# pc_kalam32_dev.net
KiCad netlist of a schematic drawn in EAGLE
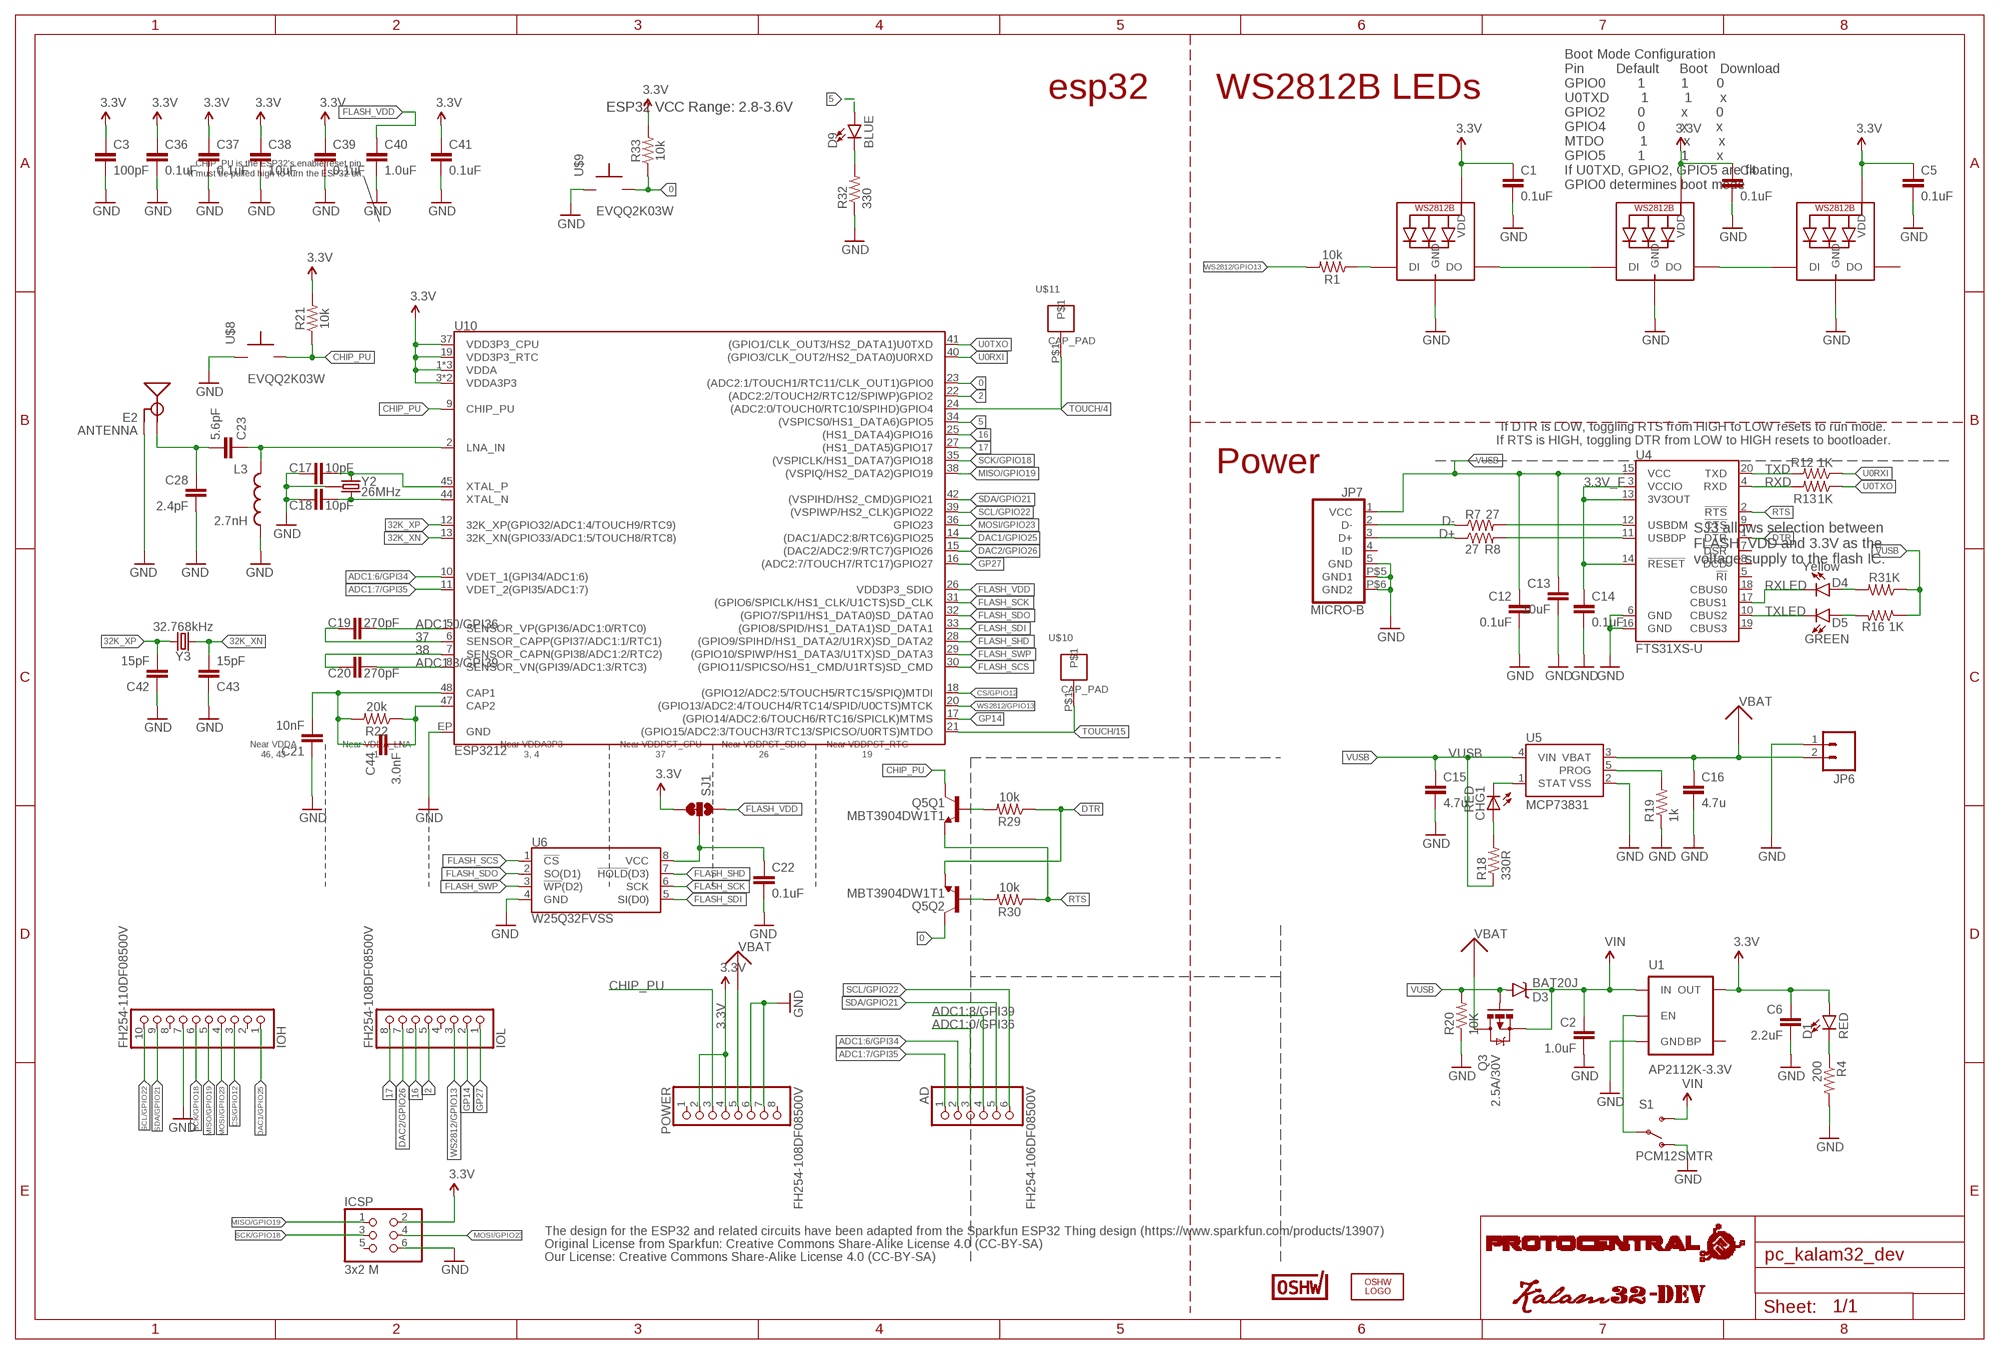
[diagram p0: schematic, sheet 1]

(export (version "E")
  (design (tool "Eeschema 10.0.6"))
  (components
    (comp (ref "AD")
      (value "FH254-106DF08500V")
      (footprint "eagle-import:1X06")
      (fields (field (name "PART_NUMBER") "20TW-535"))
      (libsource (lib "eagle-import") (part "1682_20TW-535_STD"))
    )
    (comp (ref "C1")
      (value "0.1uF")
      (footprint "eagle-import:0603")
      (libsource (lib "eagle-import") (part "0.1UF-0603-25V-(+80/-20%)"))
    )
    (comp (ref "C2")
      (value "1.0uF")
      (footprint "eagle-import:C0402")
      (libsource (lib "eagle-import") (part "C-EUC0402"))
    )
    (comp (ref "C3")
      (value "100pF")
      (footprint "eagle-import:0603")
      (libsource (lib "eagle-import") (part "100PF-0603-50V-5%"))
    )
    (comp (ref "C4")
      (value "0.1uF")
      (footprint "eagle-import:0603")
      (libsource (lib "eagle-import") (part "0.1UF-0603-25V-(+80/-20%)"))
    )
    (comp (ref "C5")
      (value "0.1uF")
      (footprint "eagle-import:0603")
      (libsource (lib "eagle-import") (part "0.1UF-0603-25V-(+80/-20%)"))
    )
    (comp (ref "C6")
      (value "2.2uF")
      (footprint "eagle-import:0603-CAP@1")
      (libsource (lib "eagle-import") (part "2.2UF-10V-20%(0603)"))
    )
    (comp (ref "C12")
      (value "0.1uF")
      (footprint "eagle-import:C0402")
      (libsource (lib "eagle-import") (part "C-EUC0402"))
    )
    (comp (ref "C13")
      (value "10uF")
      (footprint "eagle-import:C0805")
      (libsource (lib "eagle-import") (part "C-EUC0805"))
    )
    (comp (ref "C14")
      (value "0.1uF")
      (footprint "eagle-import:C0402")
      (libsource (lib "eagle-import") (part "C-EUC0402"))
    )
    (comp (ref "C15")
      (value "4.7u")
      (footprint "eagle-import:C0805")
      (libsource (lib "eagle-import") (part "C-EUC0805"))
    )
    (comp (ref "C16")
      (value "4.7u")
      (footprint "eagle-import:C0805")
      (libsource (lib "eagle-import") (part "C-EUC0805"))
    )
    (comp (ref "C17")
      (value "10pF")
      (footprint "eagle-import:0603")
      (libsource (lib "eagle-import") (part "10PF-0603-50V-5%"))
    )
    (comp (ref "C18")
      (value "10pF")
      (footprint "eagle-import:0603")
      (libsource (lib "eagle-import") (part "10PF-0603-50V-5%"))
    )
    (comp (ref "C19")
      (value "270pF")
      (footprint "eagle-import:0603")
      (libsource (lib "eagle-import") (part "270PF-50V-5%(0603)"))
    )
    (comp (ref "C20")
      (value "270pF")
      (footprint "eagle-import:0603")
      (libsource (lib "eagle-import") (part "270PF-50V-5%(0603)"))
    )
    (comp (ref "C21")
      (value "10nF")
      (footprint "eagle-import:0603")
      (libsource (lib "eagle-import") (part "10NF-0603-50V-10%"))
    )
    (comp (ref "C22")
      (value "0.1uF")
      (footprint "eagle-import:0603")
      (libsource (lib "eagle-import") (part "0.1UF-0603-25V-(+80/-20%)"))
    )
    (comp (ref "C23")
      (value "5.6pF")
      (footprint "eagle-import:0603")
      (libsource (lib "eagle-import") (part "5.6PF-50V-5%(0603)"))
    )
    (comp (ref "C28")
      (value "2.4pF")
      (footprint "eagle-import:0603")
      (libsource (lib "eagle-import") (part "2.4PF-0603-50V-5%"))
    )
    (comp (ref "C36")
      (value "0.1uF")
      (footprint "eagle-import:0603")
      (libsource (lib "eagle-import") (part "0.1UF-0603-25V-(+80/-20%)"))
    )
    (comp (ref "C37")
      (value "0.1uF")
      (footprint "eagle-import:0603")
      (libsource (lib "eagle-import") (part "0.1UF-0603-25V-(+80/-20%)"))
    )
    (comp (ref "C38")
      (value "10uF")
      (footprint "eagle-import:0603")
      (libsource (lib "eagle-import") (part "10UF-0603-6.3V-20%"))
    )
    (comp (ref "C39")
      (value "0.1uF")
      (footprint "eagle-import:0603")
      (libsource (lib "eagle-import") (part "0.1UF-0603-25V-(+80/-20%)"))
    )
    (comp (ref "C40")
      (value "1.0uF")
      (footprint "eagle-import:0603")
      (libsource (lib "eagle-import") (part "1.0UF-0603-16V-10%"))
    )
    (comp (ref "C41")
      (value "0.1uF")
      (footprint "eagle-import:0603")
      (libsource (lib "eagle-import") (part "0.1UF-0603-25V-(+80/-20%)"))
    )
    (comp (ref "C42")
      (value "15pF")
      (footprint "eagle-import:0603")
      (libsource (lib "eagle-import") (part "15PF-0603-50V-5%"))
    )
    (comp (ref "C43")
      (value "15pF")
      (footprint "eagle-import:0603")
      (libsource (lib "eagle-import") (part "15PF-0603-50V-5%"))
    )
    (comp (ref "C44")
      (value "3.0nF")
      (footprint "eagle-import:0603")
      (libsource (lib "eagle-import") (part "3.0NF-0603-50V-5%"))
    )
    (comp (ref "CHG1")
      (value "RED")
      (footprint "eagle-import:CHIPLED_0603")
      (libsource (lib "eagle-import") (part "LEDCHIPLED_0603"))
    )
    (comp (ref "D1")
      (value "RED")
      (footprint "eagle-import:LED-0603")
      (libsource (lib "eagle-import") (part "LED-RED0603"))
    )
    (comp (ref "D3")
      (value "BAT20J")
      (footprint "eagle-import:SOD-323")
      (libsource (lib "eagle-import") (part "DIODE-SCHOTTKY-BAT20J"))
    )
    (comp (ref "D4")
      (value "Yellow")
      (footprint "eagle-import:LED-0603")
      (libsource (lib "eagle-import") (part "LED-YELLOW0603"))
    )
    (comp (ref "D5")
      (value "GREEN")
      (footprint "eagle-import:LED-0603@1")
      (libsource (lib "eagle-import") (part "LED-GREEN0603"))
    )
    (comp (ref "D9")
      (value "BLUE")
      (footprint "eagle-import:LED-0603")
      (libsource (lib "eagle-import") (part "LED-BLUE0603"))
    )
    (comp (ref "E2")
      (value "ANTENNA")
      (footprint "eagle-import:TRACE_ANTENNA_2.4GHZ_25.7MM_TUNED")
      (libsource (lib "eagle-import") (part "ANTENNATRACE-TUNED"))
    )
    (comp (ref "ICSP")
      (value "3x2 M")
      (footprint "eagle-import:2X03")
      (fields (field (name "PART_NUMBER") "PH254-203DF118A00V"))
      (libsource (lib "eagle-import") (part "0114_PH254-203DF118A00V"))
    )
    (comp (ref "IOH")
      (value "FH254-110DF08500V")
      (footprint "eagle-import:1X10")
      (fields (field (name "PART_NUMBER") "20TW-537"))
      (libsource (lib "eagle-import") (part "1684_20TW-537"))
    )
    (comp (ref "IOL")
      (value "FH254-108DF08500V")
      (footprint "eagle-import:1X08")
      (fields (field (name "PART_NUMBER") "20TW-536"))
      (libsource (lib "eagle-import") (part "1683_20TW-536"))
    )
    (comp (ref "JP6")
      (value "M02-JST-2MM-SMT")
      (footprint "eagle-import:JST-2-SMD")
      (libsource (lib "eagle-import") (part "M02-JST-2MM-SMT"))
    )
    (comp (ref "JP7")
      (value "MICRO-B")
      (footprint "eagle-import:MICRO-B")
      (libsource (lib "eagle-import") (part "MICRO-B"))
    )
    (comp (ref "L3")
      (value "2.7nH")
      (footprint "eagle-import:0603")
      (libsource (lib "eagle-import") (part "INDUCTOR0603"))
    )
    (comp (ref "LED1")
      (value "WS2812B5050")
      (footprint "eagle-import:WS2812B")
      (libsource (lib "eagle-import") (part "WS2812B5050"))
    )
    (comp (ref "LED2")
      (value "WS2812B5050")
      (footprint "eagle-import:WS2812B")
      (libsource (lib "eagle-import") (part "WS2812B5050"))
    )
    (comp (ref "LED3")
      (value "WS2812B5050")
      (footprint "eagle-import:WS2812B")
      (libsource (lib "eagle-import") (part "WS2812B5050"))
    )
    (comp (ref "LOGO2")
      (value "OSHW_LOGO_FILLX0200-NT")
      (footprint "eagle-import:OSHW_FILLX200_NOTEXT")
      (libsource (lib "eagle-import") (part "OSHW_LOGO_FILLX0200-NT"))
    )
    (comp (ref "POWER")
      (value "FH254-108DF08500V")
      (footprint "eagle-import:1X08")
      (fields (field (name "PART_NUMBER") "20TW-536"))
      (libsource (lib "eagle-import") (part "1683_20TW-536"))
    )
    (comp (ref "Q3")
      (value "2.5A/30V")
      (footprint "eagle-import:SOT23-3")
      (libsource (lib "eagle-import") (part "MOSFET-PCHANNELDMG2307L"))
    )
    (comp (ref "Q5")
      (value "MBT3904DW1T1")
      (footprint "eagle-import:SC70-6")
      (libsource (lib "eagle-import") (part "MBT3904DW1T1"))
    )
    (comp (ref "R1")
      (value "10k")
      (footprint "eagle-import:0603")
      (libsource (lib "eagle-import") (part "10KOHM-1/10W-1%(0603)0603"))
    )
    (comp (ref "R3")
      (value "1K")
      (footprint "eagle-import:R0402")
      (libsource (lib "eagle-import") (part "R-US_R0402"))
    )
    (comp (ref "R4")
      (value "200")
      (footprint "eagle-import:R0402")
      (libsource (lib "eagle-import") (part "R-US_R0402"))
    )
    (comp (ref "R7")
      (value "27")
      (footprint "eagle-import:R0402")
      (libsource (lib "eagle-import") (part "R-US_R0402"))
    )
    (comp (ref "R8")
      (value "27")
      (footprint "eagle-import:R0402")
      (libsource (lib "eagle-import") (part "R-US_R0402"))
    )
    (comp (ref "R12")
      (value "1K")
      (footprint "eagle-import:R0402")
      (libsource (lib "eagle-import") (part "R-US_R0402"))
    )
    (comp (ref "R13")
      (value "1K")
      (footprint "eagle-import:R0402")
      (libsource (lib "eagle-import") (part "R-US_R0402"))
    )
    (comp (ref "R16")
      (value "1K")
      (footprint "eagle-import:R0402")
      (libsource (lib "eagle-import") (part "R-US_R0402"))
    )
    (comp (ref "R18")
      (value "330R")
      (footprint "eagle-import:R0402")
      (libsource (lib "eagle-import") (part "R-US_R0402"))
    )
    (comp (ref "R19")
      (value "1k")
      (footprint "eagle-import:R0402")
      (libsource (lib "eagle-import") (part "R-US_R0402"))
    )
    (comp (ref "R20")
      (value "10K")
      (footprint "eagle-import:R0402")
      (libsource (lib "eagle-import") (part "R-US_R0402"))
    )
    (comp (ref "R21")
      (value "10k")
      (footprint "eagle-import:0603")
      (libsource (lib "eagle-import") (part "10KOHM-1/10W-1%(0603)0603"))
    )
    (comp (ref "R22")
      (value "20k")
      (footprint "eagle-import:0603")
      (libsource (lib "eagle-import") (part "20KOHM-0603-1/10W-1%"))
    )
    (comp (ref "R29")
      (value "10k")
      (footprint "eagle-import:0603")
      (libsource (lib "eagle-import") (part "10KOHM-0603-1/10W-1%"))
    )
    (comp (ref "R30")
      (value "10k")
      (footprint "eagle-import:0603")
      (libsource (lib "eagle-import") (part "10KOHM-0603-1/10W-1%"))
    )
    (comp (ref "R32")
      (value "330")
      (footprint "eagle-import:R0805")
      (libsource (lib "eagle-import") (part "R-US_R0805"))
    )
    (comp (ref "R33")
      (value "10k")
      (footprint "eagle-import:0603")
      (libsource (lib "eagle-import") (part "10KOHM-1/10W-1%(0603)0603"))
    )
    (comp (ref "S1")
      (value "PCM12SMTR")
      (footprint "eagle-import:SWITCH-SPST-SMD-A")
      (libsource (lib "eagle-import") (part "SWITCH-SPDT-SMD-A"))
    )
    (comp (ref "SJ1")
      (value "JUMPER-PAD-3-2OF3_NC_BY_TRACE_SMALL")
      (footprint "eagle-import:PAD-JUMPER-3-2OF3_NC_BY_TRACE_YES_SILK_FULL_BOX")
      (libsource (lib "eagle-import") (part "JUMPER-PAD-3-2OF3_NC_BY_TRACE_SMALL"))
    )
    (comp (ref "U$5")
      (value "CERT-MEDIUM")
      (footprint "eagle-import:CERT-MED-SILK")
      (libsource (lib "eagle-import") (part "CERT-MEDIUM"))
    )
    (comp (ref "U$8")
      (value "EVQQ2K03W")
      (footprint "eagle-import:EVQQ2")
      (libsource (lib "eagle-import") (part "EVQQ2K03W"))
    )
    (comp (ref "U$9")
      (value "EVQQ2K03W")
      (footprint "eagle-import:EVQQ2")
      (libsource (lib "eagle-import") (part "EVQQ2K03W"))
    )
    (comp (ref "U$10")
      (value "CAP_PAD")
      (footprint "eagle-import:CAP_PAD")
      (libsource (lib "eagle-import") (part "CAP_PAD"))
    )
    (comp (ref "U$11")
      (value "CAP_PAD")
      (footprint "eagle-import:CAP_PAD")
      (libsource (lib "eagle-import") (part "CAP_PAD"))
    )
    (comp (ref "U$12")
      (value "KALAM32-DEV")
      (footprint "eagle-import:KALAM32-DEV")
      (libsource (lib "eagle-import") (part "KALAM32-DEV"))
    )
    (comp (ref "U$13")
      (value "PROTY_LOGO_WITH_TEXT")
      (footprint "eagle-import:PROTY_WITH_TEXT")
      (libsource (lib "eagle-import") (part "PROTY_LOGO_WITH_TEXT"))
    )
    (comp (ref "U1")
      (value "AP2112K-3.3V")
      (footprint "eagle-import:SOT23-5")
      (libsource (lib "eagle-import") (part "V_REG_LDOSMD"))
    )
    (comp (ref "U4")
      (value "FTS31XS-U")
      (footprint "eagle-import:SSOP20_L")
      (libsource (lib "eagle-import") (part "FT231XS"))
    )
    (comp (ref "U5")
      (value "MCP73831")
      (footprint "eagle-import:SOT23-5")
      (libsource (lib "eagle-import") (part "MCP73831"))
    )
    (comp (ref "U6")
      (value "W25Q32FVSS")
      (footprint "eagle-import:SOIC-8")
      (libsource (lib "eagle-import") (part "W25Q32FVSS"))
    )
    (comp (ref "U10")
      (value "ESP3212")
      (footprint "eagle-import:QFN48-0.4MM")
      (libsource (lib "eagle-import") (part "ESP3212"))
    )
    (comp (ref "Y2")
      (value "26MHz")
      (footprint "eagle-import:CRYSTAL-SMD-3.2X2.5")
      (libsource (lib "eagle-import") (part "CRYSTAL-GROUNDED3.2X2.5"))
    )
    (comp (ref "Y3")
      (value "32.768kHz")
      (footprint "eagle-import:CRYSTAL-SMD-3.2X1.5MM")
      (libsource (lib "eagle-import") (part "CRYSTAL-32.768KHZSMD-3.2X1.5"))
    )
  )
  (nets
    (net (code "1") (name "/3.3V_F") (class "Default")
      (node (ref "C14") (pin "1") (pinfunction "1_1") (pintype "passive"))
      (node (ref "U4") (pin "13") (pinfunction "3V3OUT_13") (pintype "bidirectional"))
      (node (ref "U4") (pin "14") (pinfunction "~{RESET}_14") (pintype "bidirectional"))
      (node (ref "U4") (pin "3") (pinfunction "VCCIO_3") (pintype "bidirectional"))
    )
    (net (code "2") (name "/37") (class "Default")
      (node (ref "C19") (pin "1") (pinfunction "1_1") (pintype "passive"))
      (node (ref "U10") (pin "6") (pinfunction "SENSOR_CAPP(GPI37/ADC1:1/RTC1)_6") (pintype "bidirectional"))
    )
    (net (code "3") (name "/38") (class "Default")
      (node (ref "C20") (pin "1") (pinfunction "1_1") (pintype "passive"))
      (node (ref "U10") (pin "7") (pinfunction "SENSOR_CAPN(GPI38/ADC1:2/RTC2)_7") (pintype "bidirectional"))
    )
    (net (code "4") (name "/ADC1:0{slash}GPI36") (class "Default")
      (node (ref "AD") (pin "3") (pinfunction "3_3") (pintype "passive"))
      (node (ref "C19") (pin "2") (pinfunction "2_2") (pintype "passive"))
      (node (ref "U10") (pin "5") (pinfunction "SENSOR_VP(GPI36/ADC1:0/RTC0)_5") (pintype "bidirectional"))
    )
    (net (code "5") (name "/ADC1:3{slash}GPI39") (class "Default")
      (node (ref "AD") (pin "4") (pinfunction "4_4") (pintype "passive"))
      (node (ref "C20") (pin "2") (pinfunction "2_2") (pintype "passive"))
      (node (ref "U10") (pin "8") (pinfunction "SENSOR_VN(GPI39/ADC1:3/RTC3)_8") (pintype "bidirectional"))
    )
    (net (code "6") (name "/D+") (class "Default")
      (node (ref "JP7") (pin "3") (pinfunction "D+_3") (pintype "bidirectional"))
      (node (ref "R8") (pin "1") (pinfunction "1_1") (pintype "passive"))
    )
    (net (code "7") (name "/D-") (class "Default")
      (node (ref "JP7") (pin "2") (pinfunction "D-_2") (pintype "bidirectional"))
      (node (ref "R7") (pin "1") (pinfunction "1_1") (pintype "passive"))
    )
    (net (code "8") (name "/RXD") (class "Default")
      (node (ref "R13") (pin "2") (pinfunction "2_2") (pintype "passive"))
      (node (ref "U4") (pin "4") (pinfunction "RXD_4") (pintype "bidirectional"))
    )
    (net (code "9") (name "/RXLED") (class "Default")
      (node (ref "D4") (pin "C") (pinfunction "C_C") (pintype "passive"))
      (node (ref "U4") (pin "17") (pinfunction "CBUS1_17") (pintype "bidirectional"))
    )
    (net (code "10") (name "/TXD") (class "Default")
      (node (ref "R12") (pin "2") (pinfunction "2_2") (pintype "passive"))
      (node (ref "U4") (pin "20") (pinfunction "TXD_20") (pintype "bidirectional"))
    )
    (net (code "11") (name "/TXLED") (class "Default")
      (node (ref "D5") (pin "C") (pinfunction "C_C") (pintype "passive"))
      (node (ref "U4") (pin "10") (pinfunction "CBUS2_10") (pintype "bidirectional"))
    )
    (net (code "12") (name "0") (class "Default")
      (node (ref "Q5") (pin "6") (pinfunction "C_6") (pintype "passive"))
      (node (ref "R33") (pin "1") (pinfunction "1_1") (pintype "passive"))
      (node (ref "U$9") (pin "P$3") (pinfunction "P$2_P$3") (pintype "bidirectional"))
      (node (ref "U10") (pin "23") (pinfunction "(ADC2:1/TOUCH1/RTC11/CLK_OUT1)GPIO0_23") (pintype "bidirectional"))
    )
    (net (code "13") (name "2") (class "Default")
      (node (ref "IOL") (pin "5") (pinfunction "5_5") (pintype "passive"))
      (node (ref "U10") (pin "22") (pinfunction "(ADC2:2/TOUCH2/RTC12/SPIWP)GPIO2_22") (pintype "bidirectional"))
    )
    (net (code "14") (name "3.3V") (class "Default")
      (node (ref "C1") (pin "1") (pinfunction "1_1") (pintype "passive"))
      (node (ref "C3") (pin "1") (pinfunction "1_1") (pintype "passive"))
      (node (ref "C36") (pin "1") (pinfunction "1_1") (pintype "passive"))
      (node (ref "C37") (pin "1") (pinfunction "1_1") (pintype "passive"))
      (node (ref "C38") (pin "1") (pinfunction "1_1") (pintype "passive"))
      (node (ref "C39") (pin "1") (pinfunction "1_1") (pintype "passive"))
      (node (ref "C4") (pin "1") (pinfunction "1_1") (pintype "passive"))
      (node (ref "C41") (pin "1") (pinfunction "1_1") (pintype "passive"))
      (node (ref "C5") (pin "1") (pinfunction "1_1") (pintype "passive"))
      (node (ref "C6") (pin "1") (pinfunction "1_1") (pintype "passive"))
      (node (ref "D1") (pin "A") (pinfunction "A_A") (pintype "passive"))
      (node (ref "ICSP") (pin "2") (pinfunction "2_2") (pintype "passive"))
      (node (ref "LED1") (pin "1-VDD") (pinfunction "VDD_1-VDD") (pintype "power_in"))
      (node (ref "LED2") (pin "1-VDD") (pinfunction "VDD_1-VDD") (pintype "power_in"))
      (node (ref "LED3") (pin "1-VDD") (pinfunction "VDD_1-VDD") (pintype "power_in"))
      (node (ref "POWER") (pin "2") (pinfunction "2_2") (pintype "passive"))
      (node (ref "POWER") (pin "4") (pinfunction "4_4") (pintype "passive"))
      (node (ref "R21") (pin "2") (pinfunction "2_2") (pintype "passive"))
      (node (ref "R33") (pin "2") (pinfunction "2_2") (pintype "passive"))
      (node (ref "SJ1") (pin "3") (pinfunction "3_3") (pintype "passive"))
      (node (ref "U1") (pin "5") (pinfunction "OUT_5") (pintype "passive"))
      (node (ref "U10") (pin "1") (pinfunction "VDDA_1") (pintype "bidirectional"))
      (node (ref "U10") (pin "19") (pinfunction "VDD3P3_RTC_19") (pintype "bidirectional"))
      (node (ref "U10") (pin "3") (pinfunction "VDDA3P3_3") (pintype "bidirectional"))
      (node (ref "U10") (pin "37") (pinfunction "VDD3P3_CPU_37") (pintype "bidirectional"))
      (node (ref "U10") (pin "4") (pinfunction "VDDA3P3_4") (pintype "bidirectional"))
      (node (ref "U10") (pin "43") (pinfunction "VDDA_43") (pintype "bidirectional"))
      (node (ref "U10") (pin "46") (pinfunction "VDDA_46") (pintype "bidirectional"))
    )
    (net (code "15") (name "5") (class "Default")
      (node (ref "D9") (pin "A") (pinfunction "A_A") (pintype "passive"))
      (node (ref "U10") (pin "34") (pinfunction "(VSPICS0/HS1_DATA6)GPIO5_34") (pintype "bidirectional"))
    )
    (net (code "16") (name "16") (class "Default")
      (node (ref "IOL") (pin "6") (pinfunction "6_6") (pintype "passive"))
      (node (ref "U10") (pin "25") (pinfunction "(HS1_DATA4)GPIO16_25") (pintype "bidirectional"))
    )
    (net (code "17") (name "17") (class "Default")
      (node (ref "IOL") (pin "8") (pinfunction "8_8") (pintype "passive"))
      (node (ref "U10") (pin "27") (pinfunction "(HS1_DATA5)GPIO17_27") (pintype "bidirectional"))
    )
    (net (code "18") (name "32K_XN") (class "Default")
      (node (ref "C43") (pin "2") (pinfunction "2_2") (pintype "passive"))
      (node (ref "U10") (pin "13") (pinfunction "32K_XN(GPIO33/ADC1:5/TOUCH8/RTC8)_13") (pintype "bidirectional"))
      (node (ref "Y3") (pin "P$2") (pinfunction "2_P$2") (pintype "passive"))
    )
    (net (code "19") (name "32K_XP") (class "Default")
      (node (ref "C42") (pin "2") (pinfunction "2_2") (pintype "passive"))
      (node (ref "U10") (pin "12") (pinfunction "32K_XP(GPIO32/ADC1:4/TOUCH9/RTC9)_12") (pintype "bidirectional"))
      (node (ref "Y3") (pin "P$1") (pinfunction "1_P$1") (pintype "passive"))
    )
    (net (code "20") (name "ADC1:6{slash}GPI34") (class "Default")
      (node (ref "AD") (pin "2") (pinfunction "2_2") (pintype "passive"))
      (node (ref "U10") (pin "10") (pinfunction "VDET_1(GPI34/ADC1:6)_10") (pintype "bidirectional"))
    )
    (net (code "21") (name "ADC1:7{slash}GPI35") (class "Default")
      (node (ref "AD") (pin "1") (pinfunction "1_1") (pintype "passive"))
      (node (ref "U10") (pin "11") (pinfunction "VDET_2(GPI35/ADC1:7)_11") (pintype "bidirectional"))
    )
    (net (code "22") (name "CHIP_PU") (class "Default")
      (node (ref "POWER") (pin "3") (pinfunction "3_3") (pintype "passive"))
      (node (ref "Q5") (pin "3") (pinfunction "C_3") (pintype "passive"))
      (node (ref "R21") (pin "1") (pinfunction "1_1") (pintype "passive"))
      (node (ref "U$8") (pin "P$3") (pinfunction "P$2_P$3") (pintype "bidirectional"))
      (node (ref "U10") (pin "9") (pinfunction "CHIP_PU_9") (pintype "bidirectional"))
    )
    (net (code "23") (name "CS{slash}GPIO12") (class "Default")
      (node (ref "IOH") (pin "3") (pinfunction "3_3") (pintype "passive"))
      (node (ref "U10") (pin "18") (pinfunction "(GPIO12/ADC2:5/TOUCH5/RTC15/SPIQ)MTDI_18") (pintype "bidirectional"))
    )
    (net (code "24") (name "DAC1{slash}GPIO25") (class "Default")
      (node (ref "IOH") (pin "1") (pinfunction "1_1") (pintype "passive"))
      (node (ref "U10") (pin "14") (pinfunction "(DAC1/ADC2:8/RTC6)GPIO25_14") (pintype "bidirectional"))
    )
    (net (code "25") (name "DAC2{slash}GPIO26") (class "Default")
      (node (ref "IOL") (pin "7") (pinfunction "7_7") (pintype "passive"))
      (node (ref "U10") (pin "15") (pinfunction "(DAC2/ADC2:9/RTC7)GPIO26_15") (pintype "bidirectional"))
    )
    (net (code "26") (name "DTR") (class "Default")
      (node (ref "Q5") (pin "1") (pinfunction "E_1") (pintype "passive"))
      (node (ref "R29") (pin "1") (pinfunction "1_1") (pintype "passive"))
      (node (ref "U4") (pin "1") (pinfunction "~{DTR}_1") (pintype "bidirectional"))
    )
    (net (code "27") (name "FLASH_SCK") (class "Default")
      (node (ref "U10") (pin "31") (pinfunction "(GPIO6/SPICLK/HS1_CLK/U1CTS)SD_CLK_31") (pintype "bidirectional"))
      (node (ref "U6") (pin "6") (pinfunction "SCK_6") (pintype "bidirectional"))
    )
    (net (code "28") (name "FLASH_SCS") (class "Default")
      (node (ref "U10") (pin "30") (pinfunction "(GPIO11/SPICSO/HS1_CMD/U1RTS)SD_CMD_30") (pintype "bidirectional"))
      (node (ref "U6") (pin "1") (pinfunction "~{CS}_1") (pintype "bidirectional"))
    )
    (net (code "29") (name "FLASH_SDI") (class "Default")
      (node (ref "U10") (pin "33") (pinfunction "(GPIO8/SPID/HS1_DATA1)SD_DATA1_33") (pintype "bidirectional"))
      (node (ref "U6") (pin "5") (pinfunction "SI(D0)_5") (pintype "bidirectional"))
    )
    (net (code "30") (name "FLASH_SDO") (class "Default")
      (node (ref "U10") (pin "32") (pinfunction "(GPIO7/SPI1/HS1_DATA0)SD_DATA0_32") (pintype "bidirectional"))
      (node (ref "U6") (pin "2") (pinfunction "SO(D1)_2") (pintype "bidirectional"))
    )
    (net (code "31") (name "FLASH_SHD") (class "Default")
      (node (ref "U10") (pin "28") (pinfunction "(GPIO9/SPIHD/HS1_DATA2/U1RX)SD_DATA2_28") (pintype "bidirectional"))
      (node (ref "U6") (pin "7") (pinfunction "~{HOLD}(D3)_7") (pintype "bidirectional"))
    )
    (net (code "32") (name "FLASH_SWP") (class "Default")
      (node (ref "U10") (pin "29") (pinfunction "(GPIO10/SPIWP/HS1_DATA3/U1TX)SD_DATA3_29") (pintype "bidirectional"))
      (node (ref "U6") (pin "3") (pinfunction "~{WP}(D2)_3") (pintype "bidirectional"))
    )
    (net (code "33") (name "FLASH_VDD") (class "Default")
      (node (ref "C40") (pin "1") (pinfunction "1_1") (pintype "passive"))
      (node (ref "SJ1") (pin "1") (pinfunction "1_1") (pintype "passive"))
      (node (ref "U10") (pin "26") (pinfunction "VDD3P3_SDIO_26") (pintype "bidirectional"))
    )
    (net (code "34") (name "GND") (class "Default")
      (node (ref "C1") (pin "2") (pinfunction "2_2") (pintype "passive"))
      (node (ref "C12") (pin "2") (pinfunction "2_2") (pintype "passive"))
      (node (ref "C13") (pin "2") (pinfunction "2_2") (pintype "passive"))
      (node (ref "C14") (pin "2") (pinfunction "2_2") (pintype "passive"))
      (node (ref "C15") (pin "2") (pinfunction "2_2") (pintype "passive"))
      (node (ref "C16") (pin "2") (pinfunction "2_2") (pintype "passive"))
      (node (ref "C17") (pin "1") (pinfunction "1_1") (pintype "passive"))
      (node (ref "C18") (pin "1") (pinfunction "1_1") (pintype "passive"))
      (node (ref "C2") (pin "2") (pinfunction "2_2") (pintype "passive"))
      (node (ref "C21") (pin "1") (pinfunction "1_1") (pintype "passive"))
      (node (ref "C22") (pin "2") (pinfunction "2_2") (pintype "passive"))
      (node (ref "C28") (pin "2") (pinfunction "2_2") (pintype "passive"))
      (node (ref "C3") (pin "2") (pinfunction "2_2") (pintype "passive"))
      (node (ref "C36") (pin "2") (pinfunction "2_2") (pintype "passive"))
      (node (ref "C37") (pin "2") (pinfunction "2_2") (pintype "passive"))
      (node (ref "C38") (pin "2") (pinfunction "2_2") (pintype "passive"))
      (node (ref "C39") (pin "2") (pinfunction "2_2") (pintype "passive"))
      (node (ref "C4") (pin "2") (pinfunction "2_2") (pintype "passive"))
      (node (ref "C40") (pin "2") (pinfunction "2_2") (pintype "passive"))
      (node (ref "C41") (pin "2") (pinfunction "2_2") (pintype "passive"))
      (node (ref "C42") (pin "1") (pinfunction "1_1") (pintype "passive"))
      (node (ref "C43") (pin "1") (pinfunction "1_1") (pintype "passive"))
      (node (ref "C5") (pin "2") (pinfunction "2_2") (pintype "passive"))
      (node (ref "C6") (pin "2") (pinfunction "2_2") (pintype "passive"))
      (node (ref "E2") (pin "GND") (pinfunction "GND_GND") (pintype "bidirectional"))
      (node (ref "E2") (pin "GND2") (pinfunction "GND_GND2") (pintype "bidirectional"))
      (node (ref "ICSP") (pin "6") (pinfunction "6_6") (pintype "passive"))
      (node (ref "IOH") (pin "7") (pinfunction "7_7") (pintype "passive"))
      (node (ref "JP6") (pin "1") (pinfunction "1_1") (pintype "passive"))
      (node (ref "JP7") (pin "5") (pinfunction "GND_5") (pintype "bidirectional"))
      (node (ref "JP7") (pin "P$5") (pinfunction "GND1_P$5") (pintype "bidirectional"))
      (node (ref "JP7") (pin "P$6") (pinfunction "GND2_P$6") (pintype "bidirectional"))
      (node (ref "L3") (pin "2") (pinfunction "2_2") (pintype "passive"))
      (node (ref "LED1") (pin "3-GND") (pinfunction "GND_3-GND") (pintype "power_in"))
      (node (ref "LED2") (pin "3-GND") (pinfunction "GND_3-GND") (pintype "power_in"))
      (node (ref "LED3") (pin "3-GND") (pinfunction "GND_3-GND") (pintype "power_in"))
      (node (ref "POWER") (pin "6") (pinfunction "6_6") (pintype "passive"))
      (node (ref "POWER") (pin "7") (pinfunction "7_7") (pintype "passive"))
      (node (ref "R19") (pin "1") (pinfunction "1_1") (pintype "passive"))
      (node (ref "R20") (pin "1") (pinfunction "1_1") (pintype "passive"))
      (node (ref "R32") (pin "1") (pinfunction "1_1") (pintype "passive"))
      (node (ref "R4") (pin "2") (pinfunction "2_2") (pintype "passive"))
      (node (ref "S1") (pin "1") (pinfunction "O_1") (pintype "passive"))
      (node (ref "U$8") (pin "P$1") (pinfunction "P$1_P$1") (pintype "bidirectional"))
      (node (ref "U$9") (pin "P$1") (pinfunction "P$1_P$1") (pintype "bidirectional"))
      (node (ref "U1") (pin "2") (pinfunction "GND_2") (pintype "input"))
      (node (ref "U10") (pin "EP") (pinfunction "GND_EP") (pintype "bidirectional"))
      (node (ref "U4") (pin "16") (pinfunction "GND_16") (pintype "bidirectional"))
      (node (ref "U4") (pin "6") (pinfunction "GND_6") (pintype "bidirectional"))
      (node (ref "U5") (pin "2") (pinfunction "VSS_2") (pintype "power_in"))
      (node (ref "U6") (pin "4") (pinfunction "GND_4") (pintype "bidirectional"))
      (node (ref "Y2") (pin "2") (pinfunction "GND_2") (pintype "passive"))
      (node (ref "Y2") (pin "4") (pinfunction "GND_4") (pintype "passive"))
    )
    (net (code "35") (name "GP14") (class "Default")
      (node (ref "IOL") (pin "2") (pinfunction "2_2") (pintype "passive"))
      (node (ref "U10") (pin "17") (pinfunction "(GPIO14/ADC2:6/TOUCH6/RTC16/SPICLK)MTMS_17") (pintype "bidirectional"))
    )
    (net (code "36") (name "GP27") (class "Default")
      (node (ref "IOL") (pin "1") (pinfunction "1_1") (pintype "passive"))
      (node (ref "U10") (pin "16") (pinfunction "(ADC2:7/TOUCH7/RTC17)GPIO27_16") (pintype "bidirectional"))
    )
    (net (code "37") (name "MISO{slash}GPIO19") (class "Default")
      (node (ref "ICSP") (pin "1") (pinfunction "1_1") (pintype "passive"))
      (node (ref "IOH") (pin "5") (pinfunction "5_5") (pintype "passive"))
      (node (ref "U10") (pin "38") (pinfunction "(VSPIQ/HS2_DATA2)GPIO19_38") (pintype "bidirectional"))
    )
    (net (code "38") (name "MOSI{slash}GPIO23") (class "Default")
      (node (ref "ICSP") (pin "4") (pinfunction "4_4") (pintype "passive"))
      (node (ref "IOH") (pin "4") (pinfunction "4_4") (pintype "passive"))
      (node (ref "U10") (pin "36") (pinfunction "GPIO23_36") (pintype "bidirectional"))
    )
    (net (code "39") (name "Net-(CHG1-PadA)") (class "Default")
      (node (ref "CHG1") (pin "A") (pinfunction "A_A") (pintype "passive"))
      (node (ref "R18") (pin "2") (pinfunction "2_2") (pintype "passive"))
    )
    (net (code "40") (name "Net-(D1-PadC)") (class "Default")
      (node (ref "D1") (pin "C") (pinfunction "C_C") (pintype "passive"))
      (node (ref "R4") (pin "1") (pinfunction "1_1") (pintype "passive"))
    )
    (net (code "41") (name "Net-(D4-PadA)") (class "Default")
      (node (ref "D4") (pin "A") (pinfunction "A_A") (pintype "passive"))
      (node (ref "R3") (pin "2") (pinfunction "2_2") (pintype "passive"))
    )
    (net (code "42") (name "Net-(D5-PadA)") (class "Default")
      (node (ref "D5") (pin "A") (pinfunction "A_A") (pintype "passive"))
      (node (ref "R16") (pin "2") (pinfunction "2_2") (pintype "passive"))
    )
    (net (code "43") (name "Net-(D9-PadC)") (class "Default")
      (node (ref "D9") (pin "C") (pinfunction "C_C") (pintype "passive"))
      (node (ref "R32") (pin "2") (pinfunction "2_2") (pintype "passive"))
    )
    (net (code "44") (name "Net-(E2-SIGNAL)") (class "Default")
      (node (ref "C23") (pin "2") (pinfunction "2_2") (pintype "passive"))
      (node (ref "C28") (pin "1") (pinfunction "1_1") (pintype "passive"))
      (node (ref "E2") (pin "ANT") (pinfunction "SIGNAL_ANT") (pintype "bidirectional"))
    )
    (net (code "45") (name "Net-(LED1-DI)") (class "Default")
      (node (ref "LED1") (pin "4-DIN") (pinfunction "DI_4-DIN") (pintype "input"))
      (node (ref "R1") (pin "1") (pinfunction "1_1") (pintype "passive"))
    )
    (net (code "46") (name "Net-(LED1-DO)") (class "Default")
      (node (ref "LED1") (pin "2-DOUT") (pinfunction "DO_2-DOUT") (pintype "output"))
      (node (ref "LED2") (pin "4-DIN") (pinfunction "DI_4-DIN") (pintype "input"))
    )
    (net (code "47") (name "Net-(LED2-DO)") (class "Default")
      (node (ref "LED2") (pin "2-DOUT") (pinfunction "DO_2-DOUT") (pintype "output"))
      (node (ref "LED3") (pin "4-DIN") (pinfunction "DI_4-DIN") (pintype "input"))
    )
    (net (code "48") (name "Net-(Q5A-B)") (class "Default")
      (node (ref "Q5") (pin "5") (pinfunction "B_5") (pintype "passive"))
      (node (ref "R29") (pin "2") (pinfunction "2_2") (pintype "passive"))
    )
    (net (code "49") (name "Net-(Q5B-B)") (class "Default")
      (node (ref "Q5") (pin "2") (pinfunction "B_2") (pintype "passive"))
      (node (ref "R30") (pin "2") (pinfunction "2_2") (pintype "passive"))
    )
    (net (code "50") (name "Net-(S1-P)") (class "Default")
      (node (ref "S1") (pin "2") (pinfunction "P_2") (pintype "passive"))
      (node (ref "U1") (pin "3") (pinfunction "EN_3") (pintype "input"))
    )
    (net (code "51") (name "Net-(U4-USBDM)") (class "Default")
      (node (ref "R7") (pin "2") (pinfunction "2_2") (pintype "passive"))
      (node (ref "U4") (pin "12") (pinfunction "USBDM_12") (pintype "bidirectional"))
    )
    (net (code "52") (name "Net-(U4-USBDP)") (class "Default")
      (node (ref "R8") (pin "2") (pinfunction "2_2") (pintype "passive"))
      (node (ref "U4") (pin "11") (pinfunction "USBDP_11") (pintype "bidirectional"))
    )
    (net (code "53") (name "Net-(U5-PROG)") (class "Default")
      (node (ref "R19") (pin "2") (pinfunction "2_2") (pintype "passive"))
      (node (ref "U5") (pin "5") (pinfunction "PROG_5") (pintype "input"))
    )
    (net (code "54") (name "Net-(U5-STAT)") (class "Default")
      (node (ref "CHG1") (pin "C") (pinfunction "C_C") (pintype "passive"))
      (node (ref "U5") (pin "1") (pinfunction "STAT_1") (pintype "output"))
    )
    (net (code "55") (name "Net-(U6-VCC)") (class "Default")
      (node (ref "C22") (pin "1") (pinfunction "1_1") (pintype "passive"))
      (node (ref "SJ1") (pin "2") (pinfunction "2_2") (pintype "passive"))
      (node (ref "U6") (pin "8") (pinfunction "VCC_8") (pintype "bidirectional"))
    )
    (net (code "56") (name "Net-(U10-CAP1)") (class "Default")
      (node (ref "C21") (pin "2") (pinfunction "2_2") (pintype "passive"))
      (node (ref "C44") (pin "1") (pinfunction "1_1") (pintype "passive"))
      (node (ref "R22") (pin "2") (pinfunction "2_2") (pintype "passive"))
      (node (ref "U10") (pin "48") (pinfunction "CAP1_48") (pintype "bidirectional"))
    )
    (net (code "57") (name "Net-(U10-CAP2)") (class "Default")
      (node (ref "C44") (pin "2") (pinfunction "2_2") (pintype "passive"))
      (node (ref "R22") (pin "1") (pinfunction "1_1") (pintype "passive"))
      (node (ref "U10") (pin "47") (pinfunction "CAP2_47") (pintype "bidirectional"))
    )
    (net (code "58") (name "Net-(U10-LNA_IN)") (class "Default")
      (node (ref "C23") (pin "1") (pinfunction "1_1") (pintype "passive"))
      (node (ref "L3") (pin "1") (pinfunction "1_1") (pintype "passive"))
      (node (ref "U10") (pin "2") (pinfunction "LNA_IN_2") (pintype "bidirectional"))
    )
    (net (code "59") (name "Net-(U10-XTAL_N)") (class "Default")
      (node (ref "C18") (pin "2") (pinfunction "2_2") (pintype "passive"))
      (node (ref "U10") (pin "44") (pinfunction "XTAL_N_44") (pintype "bidirectional"))
      (node (ref "Y2") (pin "3") (pinfunction "2_3") (pintype "passive"))
    )
    (net (code "60") (name "Net-(U10-XTAL_P)") (class "Default")
      (node (ref "C17") (pin "2") (pinfunction "2_2") (pintype "passive"))
      (node (ref "U10") (pin "45") (pinfunction "XTAL_P_45") (pintype "bidirectional"))
      (node (ref "Y2") (pin "1") (pinfunction "1_1") (pintype "passive"))
    )
    (net (code "61") (name "RTS") (class "Default")
      (node (ref "Q5") (pin "4") (pinfunction "E_4") (pintype "passive"))
      (node (ref "R30") (pin "1") (pinfunction "1_1") (pintype "passive"))
      (node (ref "U4") (pin "2") (pinfunction "~{RTS}_2") (pintype "bidirectional"))
    )
    (net (code "62") (name "SCK{slash}GPIO18") (class "Default")
      (node (ref "ICSP") (pin "3") (pinfunction "3_3") (pintype "passive"))
      (node (ref "IOH") (pin "6") (pinfunction "6_6") (pintype "passive"))
      (node (ref "U10") (pin "35") (pinfunction "(VSPICLK/HS1_DATA7)GPIO18_35") (pintype "bidirectional"))
    )
    (net (code "63") (name "SCL{slash}GPIO22") (class "Default")
      (node (ref "AD") (pin "6") (pinfunction "6_6") (pintype "passive"))
      (node (ref "IOH") (pin "10") (pinfunction "10_10") (pintype "passive"))
      (node (ref "U10") (pin "39") (pinfunction "(VSPIWP/HS2_CLK)GPIO22_39") (pintype "bidirectional"))
    )
    (net (code "64") (name "SDA{slash}GPIO21") (class "Default")
      (node (ref "AD") (pin "5") (pinfunction "5_5") (pintype "passive"))
      (node (ref "IOH") (pin "9") (pinfunction "9_9") (pintype "passive"))
      (node (ref "U10") (pin "42") (pinfunction "(VSPIHD/HS2_CMD)GPIO21_42") (pintype "bidirectional"))
    )
    (net (code "65") (name "TOUCH{slash}4") (class "Default")
      (node (ref "U$11") (pin "P$1") (pinfunction "P$1_P$1") (pintype "bidirectional"))
      (node (ref "U10") (pin "24") (pinfunction "(ADC2:0/TOUCH0/RTC10/SPIHD)GPIO4_24") (pintype "bidirectional"))
    )
    (net (code "66") (name "TOUCH{slash}15") (class "Default")
      (node (ref "U$10") (pin "P$1") (pinfunction "P$1_P$1") (pintype "bidirectional"))
      (node (ref "U10") (pin "21") (pinfunction "(GPIO15/ADC2:3/TOUCH3/RTC13/SPICSO/U0RTS)MTDO_21") (pintype "bidirectional"))
    )
    (net (code "67") (name "U0RXI") (class "Default")
      (node (ref "R12") (pin "1") (pinfunction "1_1") (pintype "passive"))
      (node (ref "U10") (pin "40") (pinfunction "(GPIO3/CLK_OUT2/HS2_DATA0)U0RXD_40") (pintype "bidirectional"))
    )
    (net (code "68") (name "U0TXO") (class "Default")
      (node (ref "R13") (pin "1") (pinfunction "1_1") (pintype "passive"))
      (node (ref "U10") (pin "41") (pinfunction "(GPIO1/CLK_OUT3/HS2_DATA1)U0TXD_41") (pintype "bidirectional"))
    )
    (net (code "69") (name "VBAT") (class "Default")
      (node (ref "C16") (pin "1") (pinfunction "1_1") (pintype "passive"))
      (node (ref "JP6") (pin "2") (pinfunction "2_2") (pintype "passive"))
      (node (ref "POWER") (pin "5") (pinfunction "5_5") (pintype "passive"))
      (node (ref "Q3") (pin "3") (pinfunction "D_3") (pintype "passive"))
      (node (ref "U5") (pin "3") (pinfunction "VBAT_3") (pintype "power_in"))
    )
    (net (code "70") (name "VIN") (class "Default")
      (node (ref "C2") (pin "1") (pinfunction "1_1") (pintype "passive"))
      (node (ref "D3") (pin "C") (pinfunction "C_C") (pintype "passive"))
      (node (ref "Q3") (pin "2") (pinfunction "S_2") (pintype "passive"))
      (node (ref "S1") (pin "3") (pinfunction "S_3") (pintype "passive"))
      (node (ref "U1") (pin "1") (pinfunction "IN_1") (pintype "input"))
    )
    (net (code "71") (name "VUSB") (class "Default")
      (node (ref "C12") (pin "1") (pinfunction "1_1") (pintype "passive"))
      (node (ref "C13") (pin "1") (pinfunction "1_1") (pintype "passive"))
      (node (ref "C15") (pin "1") (pinfunction "1_1") (pintype "passive"))
      (node (ref "D3") (pin "A") (pinfunction "A_A") (pintype "passive"))
      (node (ref "JP7") (pin "1") (pinfunction "VCC_1") (pintype "bidirectional"))
      (node (ref "Q3") (pin "1") (pinfunction "G_1") (pintype "passive"))
      (node (ref "R16") (pin "1") (pinfunction "1_1") (pintype "passive"))
      (node (ref "R18") (pin "1") (pinfunction "1_1") (pintype "passive"))
      (node (ref "R20") (pin "2") (pinfunction "2_2") (pintype "passive"))
      (node (ref "R3") (pin "1") (pinfunction "1_1") (pintype "passive"))
      (node (ref "U4") (pin "15") (pinfunction "VCC_15") (pintype "bidirectional"))
      (node (ref "U5") (pin "4") (pinfunction "VIN_4") (pintype "power_in"))
    )
    (net (code "72") (name "WS2812{slash}GPIO13") (class "Default")
      (node (ref "IOL") (pin "3") (pinfunction "3_3") (pintype "passive"))
      (node (ref "R1") (pin "2") (pinfunction "2_2") (pintype "passive"))
      (node (ref "U10") (pin "20") (pinfunction "(GPIO13/ADC2:4/TOUCH4/RTC14/SPID/U0CTS)MTCK_20") (pintype "bidirectional"))
    )
    (net (code "73") (name "unconnected-(ICSP-Pad5)") (class "Default")
      (node (ref "ICSP") (pin "5") (pinfunction "5_5") (pintype "passive"))
    )
    (net (code "74") (name "unconnected-(IOH-Pad2)") (class "Default")
      (node (ref "IOH") (pin "2") (pinfunction "2_2") (pintype "passive"))
    )
    (net (code "75") (name "unconnected-(IOH-Pad8)") (class "Default")
      (node (ref "IOH") (pin "8") (pinfunction "8_8") (pintype "passive"))
    )
    (net (code "76") (name "unconnected-(IOL-Pad4)") (class "Default")
      (node (ref "IOL") (pin "4") (pinfunction "4_4") (pintype "passive"))
    )
    (net (code "77") (name "unconnected-(JP7-ID-Pad4)") (class "Default")
      (node (ref "JP7") (pin "4") (pinfunction "ID_4") (pintype "bidirectional"))
    )
    (net (code "78") (name "unconnected-(LED3-DO-Pad2-DOUT)") (class "Default")
      (node (ref "LED3") (pin "2-DOUT") (pinfunction "DO_2-DOUT") (pintype "output"))
    )
    (net (code "79") (name "unconnected-(POWER-Pad1)") (class "Default")
      (node (ref "POWER") (pin "1") (pinfunction "1_1") (pintype "passive"))
    )
    (net (code "80") (name "unconnected-(POWER-Pad8)") (class "Default")
      (node (ref "POWER") (pin "8") (pinfunction "8_8") (pintype "passive"))
    )
    (net (code "81") (name "unconnected-(U1-BP-Pad4)") (class "Default")
      (node (ref "U1") (pin "4") (pinfunction "BP_4") (pintype "input"))
    )
    (net (code "82") (name "unconnected-(U4-CBUS0-Pad18)") (class "Default")
      (node (ref "U4") (pin "18") (pinfunction "CBUS0_18") (pintype "bidirectional"))
    )
    (net (code "83") (name "unconnected-(U4-CBUS3-Pad19)") (class "Default")
      (node (ref "U4") (pin "19") (pinfunction "CBUS3_19") (pintype "bidirectional"))
    )
    (net (code "84") (name "unconnected-(U4-~{CTS}-Pad9)") (class "Default")
      (node (ref "U4") (pin "9") (pinfunction "~{CTS}_9") (pintype "bidirectional"))
    )
    (net (code "85") (name "unconnected-(U4-~{DCD}-Pad8)") (class "Default")
      (node (ref "U4") (pin "8") (pinfunction "~{DCD}_8") (pintype "bidirectional"))
    )
    (net (code "86") (name "unconnected-(U4-~{DSR}-Pad7)") (class "Default")
      (node (ref "U4") (pin "7") (pinfunction "~{DSR}_7") (pintype "bidirectional"))
    )
    (net (code "87") (name "unconnected-(U4-~{RI}-Pad5)") (class "Default")
      (node (ref "U4") (pin "5") (pinfunction "~{RI}_5") (pintype "bidirectional"))
    )
  )
)
